# rainbow_nRlTZAmlro.net
KiCad netlist of a schematic drawn in EAGLE
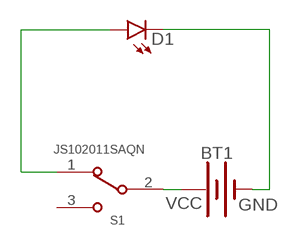
[diagram p0: schematic, sheet 1]

(export (version "E")
  (design (tool "Eeschema 10.0.6"))
  (components
    (comp (ref "BT1")
      (value "BATTERY-20MM_SMD")
      (footprint "eagle-import:BATTCON_20MM")
      (libsource (lib "eagle-import") (part "BATTERY-20MM_SMD"))
    )
    (comp (ref "D1")
      (value "LED3MM")
      (footprint "eagle-import:LED_3MM")
      (libsource (lib "eagle-import") (part "LED3MM"))
    )
    (comp (ref "S1")
      (value "JS102011SAQN")
      (footprint "eagle-import:SW_JS102011SAQN")
      (fields (field (name "MF") "C&K"))
      (libsource (lib "eagle-import") (part "JS102011SAQN"))
    )
  )
  (nets
    (net (code "1") (name "/GND") (class "Default")
      (node (ref "BT1") (pin "2") (pinfunction "-_2") (pintype "power_in"))
      (node (ref "D1") (pin "K") (pinfunction "C_K") (pintype "passive"))
    )
    (net (code "2") (name "/VCC") (class "Default")
      (node (ref "BT1") (pin "1") (pinfunction "+_1") (pintype "power_in"))
      (node (ref "S1") (pin "2") (pinfunction "2_2") (pintype "passive"))
    )
    (net (code "3") (name "Net-(D1-PadA)") (class "Default")
      (node (ref "D1") (pin "A") (pinfunction "A_A") (pintype "passive"))
      (node (ref "S1") (pin "1") (pinfunction "1_1") (pintype "passive"))
    )
    (net (code "4") (name "unconnected-(S1-Pad3)") (class "Default")
      (node (ref "S1") (pin "3") (pinfunction "3_3") (pintype "passive"))
    )
  )
)
